# SLAVE_HW.net
KiCad netlist of a schematic drawn in Altium Designer
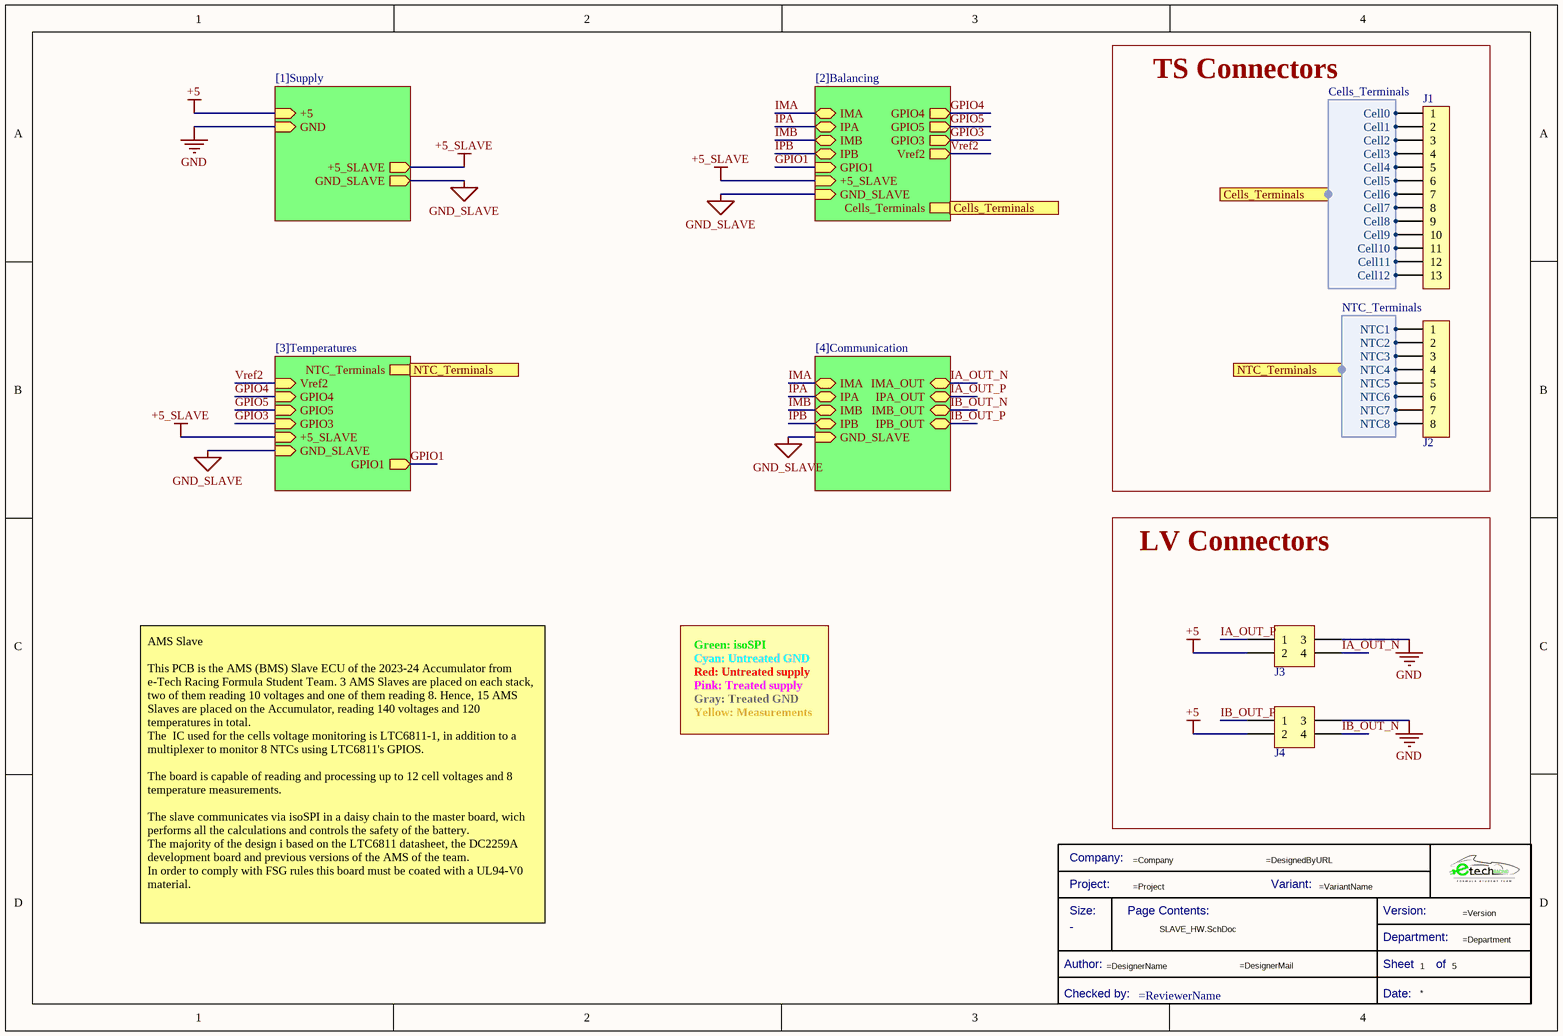
[diagram p0: SLAVE_HW.SchDoc]

(export (version "E")
  (design (tool "Eeschema 10.0.6"))
  (components
    (comp (ref "*")
      (value "Title Block_template")
      (description "Standard Title Block")
      (fields
        (field (name "SIZE") "-")
        (field (name ".CREATOR") "GP")
        (field (name ".PCBCHECK") "GP")
        (field (name ".SCHCHECK") "GP")
      )
      (libsource (lib "e-Tech_Racing") (part "Title Block_template"))
    )
    (comp (ref "J1")
      (value "61301311121")
      (footprint "J_Pinheader_1x13")
      (description "THT Vertical Pin Header WR-PHD, Pitch 2.54 mm, Single Row, 13 pins")
      (fields (field (name "MANUFACTURER") "Wurth Electronics"))
      (libsource (lib "Electromechanical") (part "J_Pinheader_1x13"))
    )
    (comp (ref "J2")
      (value "61301211121")
      (footprint "J_Pinheader_1x8")
      (description "THT Vertical Pin Header WR-PHD, Pitch 2.54 mm, Single Row, 12 pins")
      (libsource (lib "Electromechanical") (part "J_Pinheader_1x8"))
    )
    (comp (ref "J3")
      (value "J_NanoFit_2x2")
      (footprint "J_NanoFit_2x2_v")
      (description "Conn Nano-Fit Power HDR 4 POS 2.5mm Solder ST Through Hole 4 Terminal Single Port Tray")
      (libsource (lib "Electromechanical") (part "J_NanoFit_2x2"))
    )
    (comp (ref "J4")
      (value "J_NanoFit_2x2")
      (footprint "J_NanoFit_2x2_v")
      (description "Conn Nano-Fit Power HDR 4 POS 2.5mm Solder ST Through Hole 4 Terminal Single Port Tray")
      (libsource (lib "Electromechanical") (part "J_NanoFit_2x2"))
    )
  )
  (nets
    (net (code "3") (name "+5") (class "Default")
      (node (ref "J3") (pin "2") (pinfunction "2_2") (pintype "passive"))
      (node (ref "J4") (pin "2") (pinfunction "2_2") (pintype "passive"))
    )
    (net (code "5") (name "/Cell0") (class "Default")
      (node (ref "J1") (pin "1") (pinfunction "1_1") (pintype "passive"))
    )
    (net (code "6") (name "/Cell1") (class "Default")
      (node (ref "J1") (pin "2") (pinfunction "2_2") (pintype "passive"))
    )
    (net (code "7") (name "/Cell2") (class "Default")
      (node (ref "J1") (pin "3") (pinfunction "3_3") (pintype "passive"))
    )
    (net (code "8") (name "/Cell3") (class "Default")
      (node (ref "J1") (pin "4") (pinfunction "4_4") (pintype "passive"))
    )
    (net (code "9") (name "/Cell4") (class "Default")
      (node (ref "J1") (pin "5") (pinfunction "5_5") (pintype "passive"))
    )
    (net (code "10") (name "/Cell5") (class "Default")
      (node (ref "J1") (pin "6") (pinfunction "6_6") (pintype "passive"))
    )
    (net (code "11") (name "/Cell6") (class "Default")
      (node (ref "J1") (pin "7") (pinfunction "7_7") (pintype "passive"))
    )
    (net (code "12") (name "/Cell7") (class "Default")
      (node (ref "J1") (pin "8") (pinfunction "8_8") (pintype "passive"))
    )
    (net (code "13") (name "/Cell8") (class "Default")
      (node (ref "J1") (pin "9") (pinfunction "9_9") (pintype "passive"))
    )
    (net (code "14") (name "/Cell9") (class "Default")
      (node (ref "J1") (pin "10") (pinfunction "10_10") (pintype "passive"))
    )
    (net (code "15") (name "/Cell10") (class "Default")
      (node (ref "J1") (pin "11") (pinfunction "11_11") (pintype "passive"))
    )
    (net (code "16") (name "/Cell11") (class "Default")
      (node (ref "J1") (pin "12") (pinfunction "12_12") (pintype "passive"))
    )
    (net (code "17") (name "/Cell12") (class "Default")
      (node (ref "J1") (pin "13") (pinfunction "13_13") (pintype "passive"))
    )
    (net (code "22") (name "/IA_OUT_N") (class "Default")
      (node (ref "J3") (pin "4") (pinfunction "4_4") (pintype "passive"))
    )
    (net (code "23") (name "/IA_OUT_P") (class "Default")
      (node (ref "J3") (pin "1") (pinfunction "1_1") (pintype "passive"))
    )
    (net (code "24") (name "/IB_OUT_N") (class "Default")
      (node (ref "J4") (pin "4") (pinfunction "4_4") (pintype "passive"))
    )
    (net (code "25") (name "/IB_OUT_P") (class "Default")
      (node (ref "J4") (pin "1") (pinfunction "1_1") (pintype "passive"))
    )
    (net (code "30") (name "/NTC1") (class "Default")
      (node (ref "J2") (pin "1") (pinfunction "1_1") (pintype "passive"))
    )
    (net (code "31") (name "/NTC2") (class "Default")
      (node (ref "J2") (pin "2") (pinfunction "2_2") (pintype "passive"))
    )
    (net (code "32") (name "/NTC3") (class "Default")
      (node (ref "J2") (pin "3") (pinfunction "3_3") (pintype "passive"))
    )
    (net (code "33") (name "/NTC4") (class "Default")
      (node (ref "J2") (pin "4") (pinfunction "4_4") (pintype "passive"))
    )
    (net (code "34") (name "/NTC5") (class "Default")
      (node (ref "J2") (pin "5") (pinfunction "5_5") (pintype "passive"))
    )
    (net (code "35") (name "/NTC6") (class "Default")
      (node (ref "J2") (pin "6") (pinfunction "6_6") (pintype "passive"))
    )
    (net (code "36") (name "/NTC7") (class "Default")
      (node (ref "J2") (pin "7") (pinfunction "7_7") (pintype "passive"))
    )
    (net (code "37") (name "/NTC8") (class "Default")
      (node (ref "J2") (pin "8") (pinfunction "8_8") (pintype "passive"))
    )
    (net (code "41") (name "GND") (class "Default")
      (node (ref "J3") (pin "3") (pinfunction "3_3") (pintype "passive"))
      (node (ref "J4") (pin "3") (pinfunction "3_3") (pintype "passive"))
    )
  )
)
